# Memory.net
KiCad netlist of a schematic drawn in EAGLE
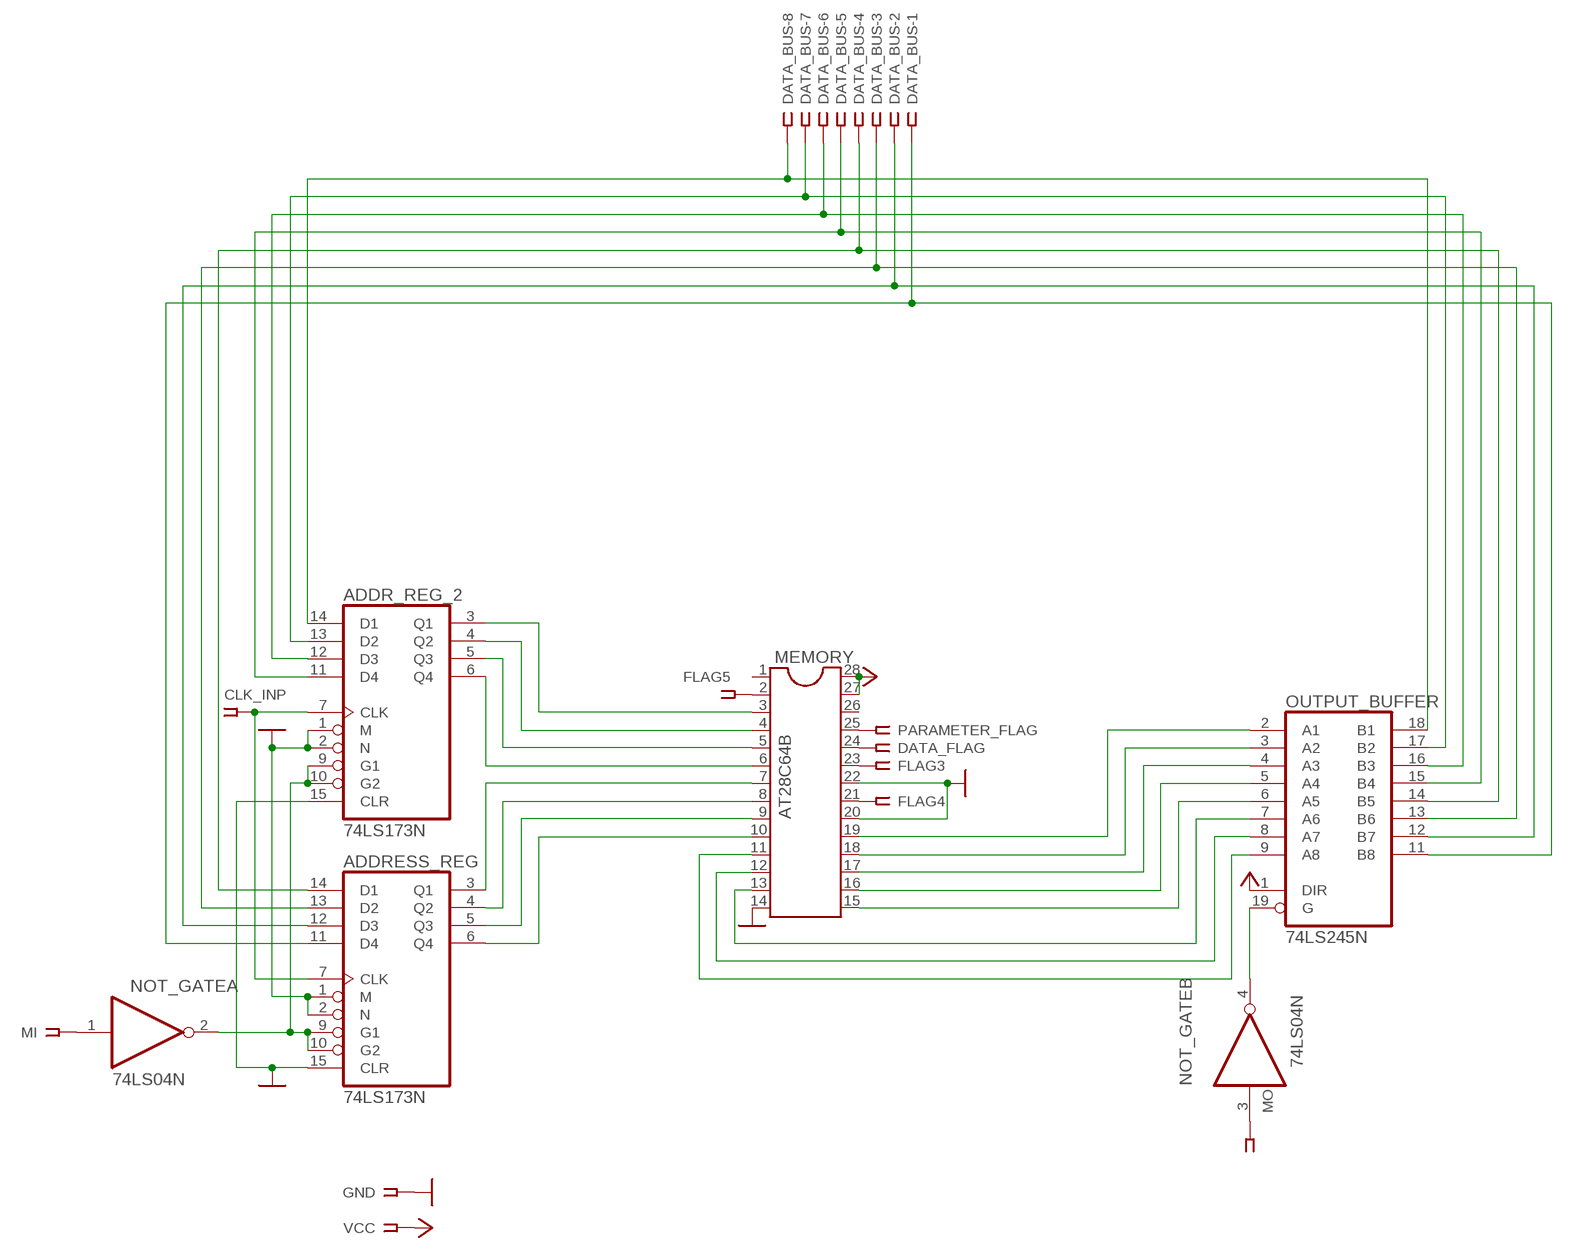
[diagram p0: schematic, sheet 1]

(export (version "E")
  (design (tool "Eeschema 10.0.6"))
  (components
    (comp (ref "ADDRESS_REG")
      (value "74LS173N")
      (footprint "eagle-import:DIL16")
      (libsource (lib "eagle-import") (part "74173NLS"))
    )
    (comp (ref "ADDR_REG_2")
      (value "74LS173N")
      (footprint "eagle-import:DIL16")
      (libsource (lib "eagle-import") (part "74173NLS"))
    )
    (comp (ref "CLK_INP")
      (value "SSW-101-02-G-S-RA")
      (footprint "eagle-import:SSW-101-02-G-S-RA")
      (fields (field (name "MF") "Samtec Inc."))
      (libsource (lib "eagle-import") (part "SSW-101-02-G-S-RA"))
    )
    (comp (ref "DATA_BUS")
      (value "SSW-108-02-G-S")
      (footprint "eagle-import:SSW-108-02-G-S")
      (fields (field (name "MF") "Samtec Inc."))
      (libsource (lib "eagle-import") (part "SSW-108-02-G-S"))
    )
    (comp (ref "DATA_FLAG")
      (value "SSW-101-02-G-S-RA")
      (footprint "eagle-import:SSW-101-02-G-S-RA")
      (fields (field (name "MF") "Samtec Inc."))
      (libsource (lib "eagle-import") (part "SSW-101-02-G-S-RA"))
    )
    (comp (ref "FLAG3")
      (value "SSW-101-02-G-S-RA")
      (footprint "eagle-import:SSW-101-02-G-S-RA")
      (fields (field (name "MF") "Samtec Inc."))
      (libsource (lib "eagle-import") (part "SSW-101-02-G-S-RA"))
    )
    (comp (ref "FLAG4")
      (value "SSW-101-02-G-S-RA")
      (footprint "eagle-import:SSW-101-02-G-S-RA")
      (fields (field (name "MF") "Samtec Inc."))
      (libsource (lib "eagle-import") (part "SSW-101-02-G-S-RA"))
    )
    (comp (ref "FLAG5")
      (value "SSW-101-02-G-S-RA")
      (footprint "eagle-import:SSW-101-02-G-S-RA")
      (fields (field (name "MF") "Samtec Inc."))
      (libsource (lib "eagle-import") (part "SSW-101-02-G-S-RA"))
    )
    (comp (ref "GND")
      (value "SSW-101-02-G-S-RA")
      (footprint "eagle-import:SSW-101-02-G-S-RA")
      (fields (field (name "MF") "Samtec Inc."))
      (libsource (lib "eagle-import") (part "SSW-101-02-G-S-RA"))
    )
    (comp (ref "MEMORY")
      (value "AT28C64B")
      (footprint "eagle-import:DIL28-6")
      (libsource (lib "eagle-import") (part "DIL28"))
    )
    (comp (ref "MI")
      (value "SSW-101-02-G-S-RA")
      (footprint "eagle-import:SSW-101-02-G-S-RA")
      (fields (field (name "MF") "Samtec Inc."))
      (libsource (lib "eagle-import") (part "SSW-101-02-G-S-RA"))
    )
    (comp (ref "MO")
      (value "SSW-101-02-G-S-RA")
      (footprint "eagle-import:SSW-101-02-G-S-RA")
      (fields (field (name "MF") "Samtec Inc."))
      (libsource (lib "eagle-import") (part "SSW-101-02-G-S-RA"))
    )
    (comp (ref "NOT_GATE")
      (value "74LS04N")
      (footprint "eagle-import:DIL14")
      (libsource (lib "eagle-import") (part "7404NLS"))
    )
    (comp (ref "OUTPUT_BUFFER")
      (value "74LS245N")
      (footprint "eagle-import:DIL20")
      (libsource (lib "eagle-import") (part "74245NLS"))
    )
    (comp (ref "PARAMETER_FLAG")
      (value "SSW-101-02-G-S-RA")
      (footprint "eagle-import:SSW-101-02-G-S-RA")
      (fields (field (name "MF") "Samtec Inc."))
      (libsource (lib "eagle-import") (part "SSW-101-02-G-S-RA"))
    )
    (comp (ref "VCC")
      (value "SSW-101-02-G-S-RA")
      (footprint "eagle-import:SSW-101-02-G-S-RA")
      (fields (field (name "MF") "Samtec Inc."))
      (libsource (lib "eagle-import") (part "SSW-101-02-G-S-RA"))
    )
  )
  (nets
    (net (code "1") (name "GND") (class "Default")
      (node (ref "ADDRESS_REG") (pin "1") (pinfunction "M_1") (pintype "input"))
      (node (ref "ADDRESS_REG") (pin "15") (pinfunction "CLR_15") (pintype "input"))
      (node (ref "ADDRESS_REG") (pin "2") (pinfunction "N_2") (pintype "input"))
      (node (ref "ADDR_REG_2") (pin "1") (pinfunction "M_1") (pintype "input"))
      (node (ref "ADDR_REG_2") (pin "15") (pinfunction "CLR_15") (pintype "input"))
      (node (ref "ADDR_REG_2") (pin "2") (pinfunction "N_2") (pintype "input"))
      (node (ref "GND") (pin "1") (pinfunction "1_1") (pintype "passive"))
      (node (ref "MEMORY") (pin "14") (pinfunction "14_14") (pintype "passive"))
      (node (ref "MEMORY") (pin "20") (pinfunction "20_20") (pintype "passive"))
      (node (ref "MEMORY") (pin "22") (pinfunction "22_22") (pintype "passive"))
    )
    (net (code "2") (name "Net-(ADDRESS_REGA-CLK)") (class "Default")
      (node (ref "ADDRESS_REG") (pin "7") (pinfunction "CLK_7") (pintype "input"))
      (node (ref "ADDR_REG_2") (pin "7") (pinfunction "CLK_7") (pintype "input"))
      (node (ref "CLK_INP") (pin "1") (pinfunction "1_1") (pintype "passive"))
    )
    (net (code "3") (name "Net-(ADDRESS_REGA-D1)") (class "Default")
      (node (ref "ADDRESS_REG") (pin "14") (pinfunction "D1_14") (pintype "input"))
      (node (ref "DATA_BUS") (pin "4") (pinfunction "1_4") (pintype "passive"))
      (node (ref "OUTPUT_BUFFER") (pin "14") (pinfunction "B5_14") (pintype "bidirectional"))
    )
    (net (code "4") (name "Net-(ADDRESS_REGA-D2)") (class "Default")
      (node (ref "ADDRESS_REG") (pin "13") (pinfunction "D2_13") (pintype "input"))
      (node (ref "DATA_BUS") (pin "3") (pinfunction "1_3") (pintype "passive"))
      (node (ref "OUTPUT_BUFFER") (pin "13") (pinfunction "B6_13") (pintype "bidirectional"))
    )
    (net (code "5") (name "Net-(ADDRESS_REGA-D3)") (class "Default")
      (node (ref "ADDRESS_REG") (pin "12") (pinfunction "D3_12") (pintype "input"))
      (node (ref "DATA_BUS") (pin "2") (pinfunction "1_2") (pintype "passive"))
      (node (ref "OUTPUT_BUFFER") (pin "12") (pinfunction "B7_12") (pintype "bidirectional"))
    )
    (net (code "6") (name "Net-(ADDRESS_REGA-D4)") (class "Default")
      (node (ref "ADDRESS_REG") (pin "11") (pinfunction "D4_11") (pintype "input"))
      (node (ref "DATA_BUS") (pin "1") (pinfunction "1_1") (pintype "passive"))
      (node (ref "OUTPUT_BUFFER") (pin "11") (pinfunction "B8_11") (pintype "bidirectional"))
    )
    (net (code "7") (name "Net-(ADDRESS_REGA-G1)") (class "Default")
      (node (ref "ADDRESS_REG") (pin "10") (pinfunction "G2_10") (pintype "input"))
      (node (ref "ADDRESS_REG") (pin "9") (pinfunction "G1_9") (pintype "input"))
      (node (ref "ADDR_REG_2") (pin "10") (pinfunction "G2_10") (pintype "input"))
      (node (ref "ADDR_REG_2") (pin "9") (pinfunction "G1_9") (pintype "input"))
      (node (ref "NOT_GATE") (pin "2") (pinfunction "O_2") (pintype "output"))
    )
    (net (code "8") (name "Net-(ADDRESS_REGA-Q1)") (class "Default")
      (node (ref "ADDRESS_REG") (pin "3") (pinfunction "Q1_3") (pintype "tri_state"))
      (node (ref "MEMORY") (pin "7") (pinfunction "7_7") (pintype "passive"))
    )
    (net (code "9") (name "Net-(ADDRESS_REGA-Q2)") (class "Default")
      (node (ref "ADDRESS_REG") (pin "4") (pinfunction "Q2_4") (pintype "tri_state"))
      (node (ref "MEMORY") (pin "8") (pinfunction "8_8") (pintype "passive"))
    )
    (net (code "10") (name "Net-(ADDRESS_REGA-Q3)") (class "Default")
      (node (ref "ADDRESS_REG") (pin "5") (pinfunction "Q3_5") (pintype "tri_state"))
      (node (ref "MEMORY") (pin "9") (pinfunction "9_9") (pintype "passive"))
    )
    (net (code "11") (name "Net-(ADDRESS_REGA-Q4)") (class "Default")
      (node (ref "ADDRESS_REG") (pin "6") (pinfunction "Q4_6") (pintype "tri_state"))
      (node (ref "MEMORY") (pin "10") (pinfunction "10_10") (pintype "passive"))
    )
    (net (code "12") (name "Net-(ADDR_REG_2A-D1)") (class "Default")
      (node (ref "ADDR_REG_2") (pin "14") (pinfunction "D1_14") (pintype "input"))
      (node (ref "DATA_BUS") (pin "8") (pinfunction "1_8") (pintype "passive"))
      (node (ref "OUTPUT_BUFFER") (pin "18") (pinfunction "B1_18") (pintype "bidirectional"))
    )
    (net (code "13") (name "Net-(ADDR_REG_2A-D2)") (class "Default")
      (node (ref "ADDR_REG_2") (pin "13") (pinfunction "D2_13") (pintype "input"))
      (node (ref "DATA_BUS") (pin "7") (pinfunction "1_7") (pintype "passive"))
      (node (ref "OUTPUT_BUFFER") (pin "17") (pinfunction "B2_17") (pintype "bidirectional"))
    )
    (net (code "14") (name "Net-(ADDR_REG_2A-D3)") (class "Default")
      (node (ref "ADDR_REG_2") (pin "12") (pinfunction "D3_12") (pintype "input"))
      (node (ref "DATA_BUS") (pin "6") (pinfunction "1_6") (pintype "passive"))
      (node (ref "OUTPUT_BUFFER") (pin "16") (pinfunction "B3_16") (pintype "bidirectional"))
    )
    (net (code "15") (name "Net-(ADDR_REG_2A-D4)") (class "Default")
      (node (ref "ADDR_REG_2") (pin "11") (pinfunction "D4_11") (pintype "input"))
      (node (ref "DATA_BUS") (pin "5") (pinfunction "1_5") (pintype "passive"))
      (node (ref "OUTPUT_BUFFER") (pin "15") (pinfunction "B4_15") (pintype "bidirectional"))
    )
    (net (code "16") (name "Net-(ADDR_REG_2A-Q1)") (class "Default")
      (node (ref "ADDR_REG_2") (pin "3") (pinfunction "Q1_3") (pintype "tri_state"))
      (node (ref "MEMORY") (pin "3") (pinfunction "3_3") (pintype "passive"))
    )
    (net (code "17") (name "Net-(ADDR_REG_2A-Q2)") (class "Default")
      (node (ref "ADDR_REG_2") (pin "4") (pinfunction "Q2_4") (pintype "tri_state"))
      (node (ref "MEMORY") (pin "4") (pinfunction "4_4") (pintype "passive"))
    )
    (net (code "18") (name "Net-(ADDR_REG_2A-Q3)") (class "Default")
      (node (ref "ADDR_REG_2") (pin "5") (pinfunction "Q3_5") (pintype "tri_state"))
      (node (ref "MEMORY") (pin "5") (pinfunction "5_5") (pintype "passive"))
    )
    (net (code "19") (name "Net-(ADDR_REG_2A-Q4)") (class "Default")
      (node (ref "ADDR_REG_2") (pin "6") (pinfunction "Q4_6") (pintype "tri_state"))
      (node (ref "MEMORY") (pin "6") (pinfunction "6_6") (pintype "passive"))
    )
    (net (code "20") (name "Net-(DATA_FLAG-Pad1)") (class "Default")
      (node (ref "DATA_FLAG") (pin "1") (pinfunction "1_1") (pintype "passive"))
      (node (ref "MEMORY") (pin "24") (pinfunction "24_24") (pintype "passive"))
    )
    (net (code "21") (name "Net-(FLAG3-Pad1)") (class "Default")
      (node (ref "FLAG3") (pin "1") (pinfunction "1_1") (pintype "passive"))
      (node (ref "MEMORY") (pin "23") (pinfunction "23_23") (pintype "passive"))
    )
    (net (code "22") (name "Net-(FLAG4-Pad1)") (class "Default")
      (node (ref "FLAG4") (pin "1") (pinfunction "1_1") (pintype "passive"))
      (node (ref "MEMORY") (pin "21") (pinfunction "21_21") (pintype "passive"))
    )
    (net (code "23") (name "Net-(FLAG5-Pad1)") (class "Default")
      (node (ref "FLAG5") (pin "1") (pinfunction "1_1") (pintype "passive"))
      (node (ref "MEMORY") (pin "2") (pinfunction "2_2") (pintype "passive"))
    )
    (net (code "24") (name "Net-(MEMORY-Pad25)") (class "Default")
      (node (ref "MEMORY") (pin "25") (pinfunction "25_25") (pintype "passive"))
      (node (ref "PARAMETER_FLAG") (pin "1") (pinfunction "1_1") (pintype "passive"))
    )
    (net (code "25") (name "Net-(NOT_GATEA-I)") (class "Default")
      (node (ref "MI") (pin "1") (pinfunction "1_1") (pintype "passive"))
      (node (ref "NOT_GATE") (pin "1") (pinfunction "I_1") (pintype "input"))
    )
    (net (code "26") (name "Net-(NOT_GATEB-I)") (class "Default")
      (node (ref "MO") (pin "1") (pinfunction "1_1") (pintype "passive"))
      (node (ref "NOT_GATE") (pin "3") (pinfunction "I_3") (pintype "input"))
    )
    (net (code "27") (name "Net-(NOT_GATEB-O)") (class "Default")
      (node (ref "NOT_GATE") (pin "4") (pinfunction "O_4") (pintype "output"))
      (node (ref "OUTPUT_BUFFER") (pin "19") (pinfunction "G_19") (pintype "input"))
    )
    (net (code "28") (name "Net-(OUTPUT_BUFFERA-A1)") (class "Default")
      (node (ref "MEMORY") (pin "19") (pinfunction "19_19") (pintype "passive"))
      (node (ref "OUTPUT_BUFFER") (pin "2") (pinfunction "A1_2") (pintype "bidirectional"))
    )
    (net (code "29") (name "Net-(OUTPUT_BUFFERA-A2)") (class "Default")
      (node (ref "MEMORY") (pin "18") (pinfunction "18_18") (pintype "passive"))
      (node (ref "OUTPUT_BUFFER") (pin "3") (pinfunction "A2_3") (pintype "bidirectional"))
    )
    (net (code "30") (name "Net-(OUTPUT_BUFFERA-A3)") (class "Default")
      (node (ref "MEMORY") (pin "17") (pinfunction "17_17") (pintype "passive"))
      (node (ref "OUTPUT_BUFFER") (pin "4") (pinfunction "A3_4") (pintype "bidirectional"))
    )
    (net (code "31") (name "Net-(OUTPUT_BUFFERA-A4)") (class "Default")
      (node (ref "MEMORY") (pin "16") (pinfunction "16_16") (pintype "passive"))
      (node (ref "OUTPUT_BUFFER") (pin "5") (pinfunction "A4_5") (pintype "bidirectional"))
    )
    (net (code "32") (name "Net-(OUTPUT_BUFFERA-A5)") (class "Default")
      (node (ref "MEMORY") (pin "15") (pinfunction "15_15") (pintype "passive"))
      (node (ref "OUTPUT_BUFFER") (pin "6") (pinfunction "A5_6") (pintype "bidirectional"))
    )
    (net (code "33") (name "Net-(OUTPUT_BUFFERA-A6)") (class "Default")
      (node (ref "MEMORY") (pin "13") (pinfunction "13_13") (pintype "passive"))
      (node (ref "OUTPUT_BUFFER") (pin "7") (pinfunction "A6_7") (pintype "bidirectional"))
    )
    (net (code "34") (name "Net-(OUTPUT_BUFFERA-A7)") (class "Default")
      (node (ref "MEMORY") (pin "12") (pinfunction "12_12") (pintype "passive"))
      (node (ref "OUTPUT_BUFFER") (pin "8") (pinfunction "A7_8") (pintype "bidirectional"))
    )
    (net (code "35") (name "Net-(OUTPUT_BUFFERA-A8)") (class "Default")
      (node (ref "MEMORY") (pin "11") (pinfunction "11_11") (pintype "passive"))
      (node (ref "OUTPUT_BUFFER") (pin "9") (pinfunction "A8_9") (pintype "bidirectional"))
    )
    (net (code "36") (name "VCC") (class "Default")
      (node (ref "MEMORY") (pin "27") (pinfunction "27_27") (pintype "passive"))
      (node (ref "MEMORY") (pin "28") (pinfunction "28_28") (pintype "passive"))
      (node (ref "OUTPUT_BUFFER") (pin "1") (pinfunction "DIR_1") (pintype "input"))
      (node (ref "VCC") (pin "1") (pinfunction "1_1") (pintype "passive"))
    )
    (net (code "37") (name "unconnected-(MEMORY-Pad1)") (class "Default")
      (node (ref "MEMORY") (pin "1") (pinfunction "1_1") (pintype "passive"))
    )
    (net (code "38") (name "unconnected-(MEMORY-Pad26)") (class "Default")
      (node (ref "MEMORY") (pin "26") (pinfunction "26_26") (pintype "passive"))
    )
  )
)
